# Adafruit_Bluefruit_LE_USB_Friend.net
KiCad netlist of a schematic drawn in EAGLE
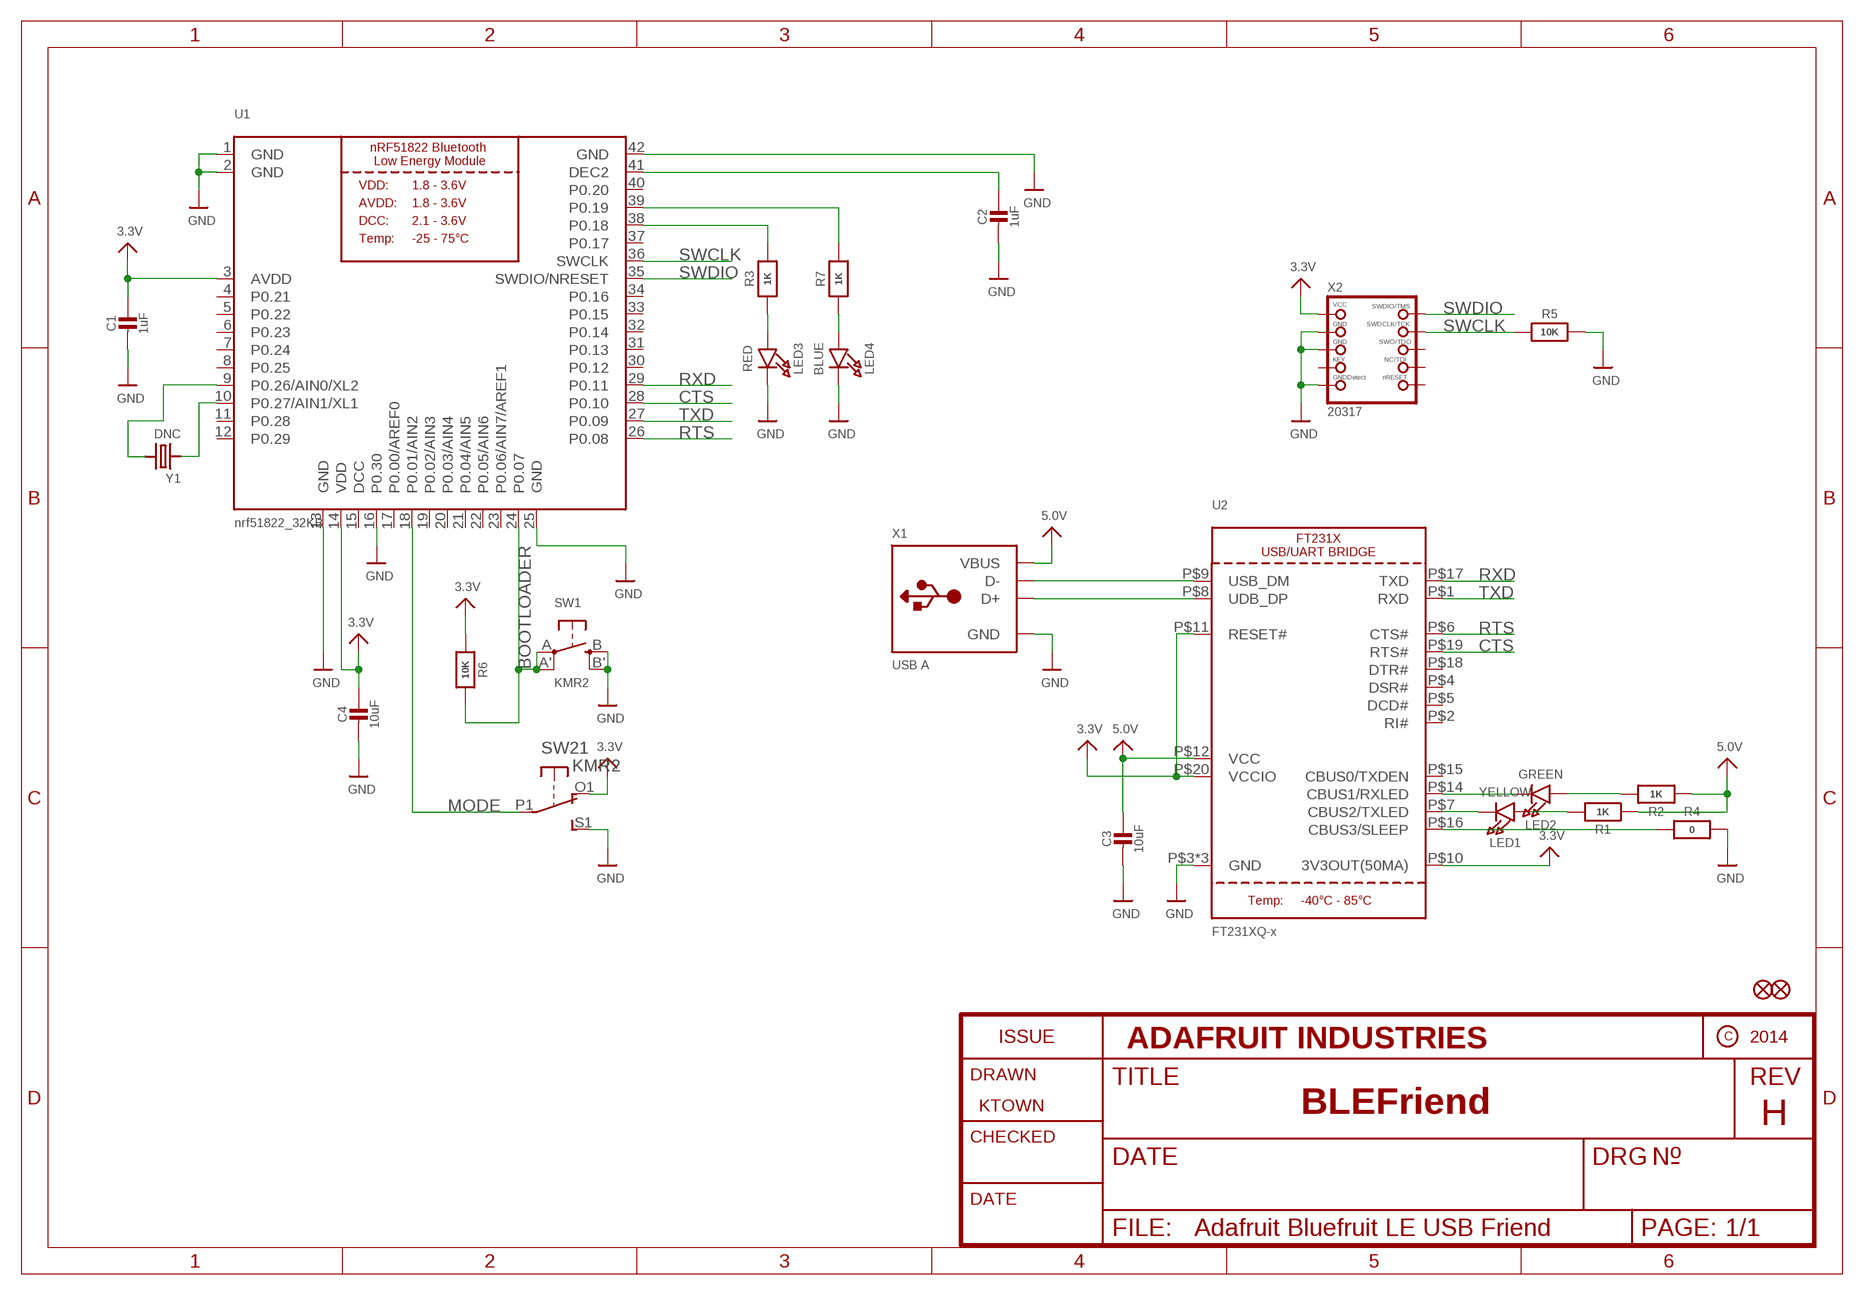
[diagram p0: schematic, sheet 1]

(export (version "E")
  (design (tool "Eeschema 10.0.6"))
  (components
    (comp (ref "C1")
      (value "1uF")
      (footprint "eagle-import:_0805MP")
      (libsource (lib "eagle-import") (part "CAP_CERAMIC_0805MP"))
    )
    (comp (ref "C2")
      (value "1uF")
      (footprint "eagle-import:_0805MP")
      (libsource (lib "eagle-import") (part "CAP_CERAMIC_0805MP"))
    )
    (comp (ref "C3")
      (value "10uF")
      (footprint "eagle-import:_0805MP")
      (libsource (lib "eagle-import") (part "CAP_CERAMIC_0805MP"))
    )
    (comp (ref "C4")
      (value "10uF")
      (footprint "eagle-import:_0805MP")
      (libsource (lib "eagle-import") (part "CAP_CERAMIC_0805MP"))
    )
    (comp (ref "FID1")
      (value "FIDUCIAL\"\"")
      (footprint "eagle-import:FIDUCIAL_1MM")
      (libsource (lib "eagle-import") (part "FIDUCIAL{dblquote}{dblquote}"))
    )
    (comp (ref "FID2")
      (value "FIDUCIAL\"\"")
      (footprint "eagle-import:FIDUCIAL_1MM")
      (libsource (lib "eagle-import") (part "FIDUCIAL{dblquote}{dblquote}"))
    )
    (comp (ref "LED1")
      (value "YELLOW")
      (footprint "eagle-import:CHIPLED_0805_NOOUTLINE")
      (libsource (lib "eagle-import") (part "LED0805_NOOUTLINE"))
    )
    (comp (ref "LED2")
      (value "GREEN")
      (footprint "eagle-import:CHIPLED_0805_NOOUTLINE")
      (libsource (lib "eagle-import") (part "LED0805_NOOUTLINE"))
    )
    (comp (ref "LED3")
      (value "RED")
      (footprint "eagle-import:CHIPLED_0805_NOOUTLINE")
      (libsource (lib "eagle-import") (part "LED0805_NOOUTLINE"))
    )
    (comp (ref "LED4")
      (value "BLUE")
      (footprint "eagle-import:CHIPLED_0805_NOOUTLINE")
      (libsource (lib "eagle-import") (part "LED0805_NOOUTLINE"))
    )
    (comp (ref "R1")
      (value "1K")
      (footprint "eagle-import:_0805MP")
      (libsource (lib "eagle-import") (part "RESISTOR_0805MP"))
    )
    (comp (ref "R2")
      (value "1K")
      (footprint "eagle-import:_0805MP")
      (libsource (lib "eagle-import") (part "RESISTOR_0805MP"))
    )
    (comp (ref "R3")
      (value "1K")
      (footprint "eagle-import:_0805MP")
      (libsource (lib "eagle-import") (part "RESISTOR_0805MP"))
    )
    (comp (ref "R4")
      (value "0")
      (footprint "eagle-import:_0805MP")
      (libsource (lib "eagle-import") (part "RESISTOR_0805MP"))
    )
    (comp (ref "R5")
      (value "10K")
      (footprint "eagle-import:_0805MP")
      (libsource (lib "eagle-import") (part "RESISTOR_0805MP"))
    )
    (comp (ref "R6")
      (value "10K")
      (footprint "eagle-import:_0805MP")
      (libsource (lib "eagle-import") (part "RESISTOR_0805MP"))
    )
    (comp (ref "R7")
      (value "1K")
      (footprint "eagle-import:_0805MP")
      (libsource (lib "eagle-import") (part "RESISTOR_0805MP"))
    )
    (comp (ref "SW1")
      (value "KMR2")
      (footprint "eagle-import:BTN_KMR2_4.6X2.8")
      (libsource (lib "eagle-import") (part "SWITCH_TACT_SMT4.6X2.8"))
    )
    (comp (ref "SW2")
      (value "KMR2")
      (footprint "eagle-import:EG1390")
      (libsource (lib "eagle-import") (part "DPDT-EG1390"))
    )
    (comp (ref "U1")
      (value "nrf51822_32KB")
      (footprint "eagle-import:BLE_MODULE_RAYTAC_MDBT40")
      (libsource (lib "eagle-import") (part "BLE_MODULE_RAYTAC_MDBT40"))
    )
    (comp (ref "U2")
      (value "FT231XQ-x")
      (footprint "eagle-import:QFN20_4MM")
      (libsource (lib "eagle-import") (part "FT231X"))
    )
    (comp (ref "X1")
      (value "USB A")
      (footprint "eagle-import:USB_A-THM")
      (libsource (lib "eagle-import") (part "USB_TYPEA_CLIENTTHM"))
    )
    (comp (ref "X2")
      (value "20317")
      (footprint "eagle-import:2X05_1.27MM_BOX_POSTS")
      (libsource (lib "eagle-import") (part "JTAG-CORTEXBOXPOSTS"))
    )
    (comp (ref "Y1")
      (value "DNC")
      (footprint "eagle-import:CRYSTAL_CYL_2X6MM_SMT")
      (libsource (lib "eagle-import") (part "CRYSTAL2.0X6.0_32.768"))
    )
  )
  (nets
    (net (code "1") (name "/BOOTLOADER") (class "Default")
      (node (ref "R6") (pin "2") (pinfunction "2_2") (pintype "passive"))
      (node (ref "SW1") (pin "A") (pinfunction "P_A") (pintype "passive"))
      (node (ref "SW1") (pin "A'") (pinfunction "P1_A'") (pintype "passive"))
      (node (ref "U1") (pin "24") (pinfunction "P0.07_24") (pintype "bidirectional"))
    )
    (net (code "2") (name "/CTS") (class "Default")
      (node (ref "U1") (pin "28") (pinfunction "P0.10_28") (pintype "bidirectional"))
      (node (ref "U2") (pin "P$19") (pinfunction "RTS#_P$19") (pintype "output"))
    )
    (net (code "3") (name "/DCC") (class "Default")
      (node (ref "U1") (pin "15") (pinfunction "DCC_15") (pintype "power_in"))
    )
    (net (code "4") (name "/MODE") (class "Default")
      (node (ref "SW2") (pin "P1") (pinfunction "P_P1") (pintype "passive"))
      (node (ref "U1") (pin "18") (pinfunction "P0.01/AIN2_18") (pintype "bidirectional"))
    )
    (net (code "5") (name "/RTS") (class "Default")
      (node (ref "U1") (pin "26") (pinfunction "P0.08_26") (pintype "bidirectional"))
      (node (ref "U2") (pin "P$6") (pinfunction "CTS#_P$6") (pintype "input"))
    )
    (net (code "6") (name "/RXD") (class "Default")
      (node (ref "U1") (pin "29") (pinfunction "P0.11_29") (pintype "bidirectional"))
      (node (ref "U2") (pin "P$17") (pinfunction "TXD_P$17") (pintype "output"))
    )
    (net (code "7") (name "/SWCLK") (class "Default")
      (node (ref "R5") (pin "1") (pinfunction "1_1") (pintype "passive"))
      (node (ref "U1") (pin "36") (pinfunction "SWCLK_36") (pintype "bidirectional"))
      (node (ref "X2") (pin "4") (pinfunction "SWDCLK_4") (pintype "bidirectional"))
    )
    (net (code "8") (name "/SWDIO") (class "Default")
      (node (ref "U1") (pin "35") (pinfunction "SWDIO/NRESET_35") (pintype "bidirectional"))
      (node (ref "X2") (pin "2") (pinfunction "SWDIO_2") (pintype "bidirectional"))
    )
    (net (code "9") (name "/TXD") (class "Default")
      (node (ref "U1") (pin "27") (pinfunction "P0.09_27") (pintype "bidirectional"))
      (node (ref "U2") (pin "P$1") (pinfunction "RXD_P$1") (pintype "input"))
    )
    (net (code "10") (name "3.3V") (class "Default")
      (node (ref "C1") (pin "1") (pinfunction "1_1") (pintype "passive"))
      (node (ref "C4") (pin "1") (pinfunction "1_1") (pintype "passive"))
      (node (ref "R6") (pin "1") (pinfunction "1_1") (pintype "passive"))
      (node (ref "SW2") (pin "O1") (pinfunction "O_O1") (pintype "passive"))
      (node (ref "U1") (pin "14") (pinfunction "VDD_14") (pintype "power_in"))
      (node (ref "U1") (pin "3") (pinfunction "AVDD_3") (pintype "power_in"))
      (node (ref "U2") (pin "P$10") (pinfunction "3V3OUT(50MA)_P$10") (pintype "power_in"))
      (node (ref "U2") (pin "P$11") (pinfunction "RESET#_P$11") (pintype "input"))
      (node (ref "U2") (pin "P$20") (pinfunction "VCCIO_P$20") (pintype "power_in"))
      (node (ref "X2") (pin "1") (pinfunction "VCC_1") (pintype "power_in"))
    )
    (net (code "11") (name "5.0V") (class "Default")
      (node (ref "C3") (pin "1") (pinfunction "1_1") (pintype "passive"))
      (node (ref "R1") (pin "1") (pinfunction "1_1") (pintype "passive"))
      (node (ref "R2") (pin "1") (pinfunction "1_1") (pintype "passive"))
      (node (ref "U2") (pin "P$12") (pinfunction "VCC_P$12") (pintype "power_in"))
      (node (ref "X1") (pin "VBUS") (pinfunction "VBUS_VBUS") (pintype "power_in"))
    )
    (net (code "12") (name "GND") (class "Default")
      (node (ref "C1") (pin "2") (pinfunction "2_2") (pintype "passive"))
      (node (ref "C2") (pin "2") (pinfunction "2_2") (pintype "passive"))
      (node (ref "C3") (pin "2") (pinfunction "2_2") (pintype "passive"))
      (node (ref "C4") (pin "2") (pinfunction "2_2") (pintype "passive"))
      (node (ref "LED3") (pin "C") (pinfunction "C_C") (pintype "passive"))
      (node (ref "LED4") (pin "C") (pinfunction "C_C") (pintype "passive"))
      (node (ref "R4") (pin "2") (pinfunction "2_2") (pintype "passive"))
      (node (ref "R5") (pin "2") (pinfunction "2_2") (pintype "passive"))
      (node (ref "SW1") (pin "B") (pinfunction "S_B") (pintype "passive"))
      (node (ref "SW1") (pin "B'") (pinfunction "S1_B'") (pintype "passive"))
      (node (ref "SW2") (pin "S1") (pinfunction "S_S1") (pintype "passive"))
      (node (ref "U1") (pin "1") (pinfunction "GND_1") (pintype "power_in"))
      (node (ref "U1") (pin "13") (pinfunction "GND_13") (pintype "power_in"))
      (node (ref "U1") (pin "16") (pinfunction "P0.30_16") (pintype "bidirectional"))
      (node (ref "U1") (pin "2") (pinfunction "GND_2") (pintype "power_in"))
      (node (ref "U1") (pin "25") (pinfunction "GND_25") (pintype "power_in"))
      (node (ref "U1") (pin "42") (pinfunction "GND_42") (pintype "power_in"))
      (node (ref "U2") (pin "P$13") (pinfunction "GND_P$13") (pintype "power_in"))
      (node (ref "U2") (pin "P$21") (pinfunction "GND_P$21") (pintype "power_in"))
      (node (ref "U2") (pin "P$3") (pinfunction "GND_P$3") (pintype "power_in"))
      (node (ref "X1") (pin "GND") (pinfunction "GND_GND") (pintype "power_in"))
      (node (ref "X2") (pin "3") (pinfunction "GND_3") (pintype "power_in"))
      (node (ref "X2") (pin "5") (pinfunction "GND_5") (pintype "power_in"))
      (node (ref "X2") (pin "9") (pinfunction "GNDDETECT_9") (pintype "bidirectional"))
    )
    (net (code "13") (name "Net-(LED1-PadA)") (class "Default")
      (node (ref "LED1") (pin "A") (pinfunction "A_A") (pintype "passive"))
      (node (ref "R1") (pin "2") (pinfunction "2_2") (pintype "passive"))
    )
    (net (code "14") (name "Net-(LED2-PadA)") (class "Default")
      (node (ref "LED2") (pin "A") (pinfunction "A_A") (pintype "passive"))
      (node (ref "R2") (pin "2") (pinfunction "2_2") (pintype "passive"))
    )
    (net (code "15") (name "Net-(LED3-PadA)") (class "Default")
      (node (ref "LED3") (pin "A") (pinfunction "A_A") (pintype "passive"))
      (node (ref "R3") (pin "1") (pinfunction "1_1") (pintype "passive"))
    )
    (net (code "16") (name "Net-(LED4-PadA)") (class "Default")
      (node (ref "LED4") (pin "A") (pinfunction "A_A") (pintype "passive"))
      (node (ref "R7") (pin "1") (pinfunction "1_1") (pintype "passive"))
    )
    (net (code "17") (name "Net-(U1-DEC2)") (class "Default")
      (node (ref "C2") (pin "1") (pinfunction "1_1") (pintype "passive"))
      (node (ref "U1") (pin "41") (pinfunction "DEC2_41") (pintype "power_in"))
    )
    (net (code "18") (name "Net-(U1-P0.18)") (class "Default")
      (node (ref "R3") (pin "2") (pinfunction "2_2") (pintype "passive"))
      (node (ref "U1") (pin "38") (pinfunction "P0.18_38") (pintype "bidirectional"))
    )
    (net (code "19") (name "Net-(U1-P0.19)") (class "Default")
      (node (ref "R7") (pin "2") (pinfunction "2_2") (pintype "passive"))
      (node (ref "U1") (pin "39") (pinfunction "P0.19_39") (pintype "bidirectional"))
    )
    (net (code "20") (name "Net-(U1-P0.26{slash}AIN0{slash}XL2)") (class "Default")
      (node (ref "U1") (pin "9") (pinfunction "P0.26/AIN0/XL2_9") (pintype "bidirectional"))
      (node (ref "Y1") (pin "2") (pinfunction "2_2") (pintype "passive"))
    )
    (net (code "21") (name "Net-(U1-P0.27{slash}AIN1{slash}XL1)") (class "Default")
      (node (ref "U1") (pin "10") (pinfunction "P0.27/AIN1/XL1_10") (pintype "bidirectional"))
      (node (ref "Y1") (pin "1") (pinfunction "1_1") (pintype "passive"))
    )
    (net (code "22") (name "Net-(U2-CBUS1{slash}RXLED)") (class "Default")
      (node (ref "LED2") (pin "C") (pinfunction "C_C") (pintype "passive"))
      (node (ref "U2") (pin "P$14") (pinfunction "CBUS1/RXLED_P$14") (pintype "bidirectional"))
    )
    (net (code "23") (name "Net-(U2-CBUS2{slash}TXLED)") (class "Default")
      (node (ref "LED1") (pin "C") (pinfunction "C_C") (pintype "passive"))
      (node (ref "U2") (pin "P$7") (pinfunction "CBUS2/TXLED_P$7") (pintype "bidirectional"))
    )
    (net (code "24") (name "Net-(U2-CBUS3{slash}SLEEP)") (class "Default")
      (node (ref "R4") (pin "1") (pinfunction "1_1") (pintype "passive"))
      (node (ref "U2") (pin "P$16") (pinfunction "CBUS3/SLEEP_P$16") (pintype "bidirectional"))
    )
    (net (code "25") (name "Net-(U2-UDB_DP)") (class "Default")
      (node (ref "U2") (pin "P$8") (pinfunction "UDB_DP_P$8") (pintype "input"))
      (node (ref "X1") (pin "D+") (pinfunction "D+_D+") (pintype "bidirectional"))
    )
    (net (code "26") (name "Net-(U2-USB_DM)") (class "Default")
      (node (ref "U2") (pin "P$9") (pinfunction "USB_DM_P$9") (pintype "input"))
      (node (ref "X1") (pin "D-") (pinfunction "D-_D-") (pintype "bidirectional"))
    )
    (net (code "27") (name "unconnected-(U1-P0.00{slash}AREF0-Pad17)") (class "Default")
      (node (ref "U1") (pin "17") (pinfunction "P0.00/AREF0_17") (pintype "bidirectional"))
    )
    (net (code "28") (name "unconnected-(U1-P0.02{slash}AIN3-Pad19)") (class "Default")
      (node (ref "U1") (pin "19") (pinfunction "P0.02/AIN3_19") (pintype "bidirectional"))
    )
    (net (code "29") (name "unconnected-(U1-P0.03{slash}AIN4-Pad20)") (class "Default")
      (node (ref "U1") (pin "20") (pinfunction "P0.03/AIN4_20") (pintype "bidirectional"))
    )
    (net (code "30") (name "unconnected-(U1-P0.04{slash}AIN5-Pad21)") (class "Default")
      (node (ref "U1") (pin "21") (pinfunction "P0.04/AIN5_21") (pintype "bidirectional"))
    )
    (net (code "31") (name "unconnected-(U1-P0.05{slash}AIN6-Pad22)") (class "Default")
      (node (ref "U1") (pin "22") (pinfunction "P0.05/AIN6_22") (pintype "bidirectional"))
    )
    (net (code "32") (name "unconnected-(U1-P0.06{slash}AIN7{slash}AREF1-Pad23)") (class "Default")
      (node (ref "U1") (pin "23") (pinfunction "P0.06/AIN7/AREF1_23") (pintype "bidirectional"))
    )
    (net (code "33") (name "unconnected-(U1-P0.12-Pad30)") (class "Default")
      (node (ref "U1") (pin "30") (pinfunction "P0.12_30") (pintype "bidirectional"))
    )
    (net (code "34") (name "unconnected-(U1-P0.13-Pad31)") (class "Default")
      (node (ref "U1") (pin "31") (pinfunction "P0.13_31") (pintype "bidirectional"))
    )
    (net (code "35") (name "unconnected-(U1-P0.14-Pad32)") (class "Default")
      (node (ref "U1") (pin "32") (pinfunction "P0.14_32") (pintype "bidirectional"))
    )
    (net (code "36") (name "unconnected-(U1-P0.15-Pad33)") (class "Default")
      (node (ref "U1") (pin "33") (pinfunction "P0.15_33") (pintype "bidirectional"))
    )
    (net (code "37") (name "unconnected-(U1-P0.16-Pad34)") (class "Default")
      (node (ref "U1") (pin "34") (pinfunction "P0.16_34") (pintype "bidirectional"))
    )
    (net (code "38") (name "unconnected-(U1-P0.17-Pad37)") (class "Default")
      (node (ref "U1") (pin "37") (pinfunction "P0.17_37") (pintype "bidirectional"))
    )
    (net (code "39") (name "unconnected-(U1-P0.20-Pad40)") (class "Default")
      (node (ref "U1") (pin "40") (pinfunction "P0.20_40") (pintype "bidirectional"))
    )
    (net (code "40") (name "unconnected-(U1-P0.21-Pad4)") (class "Default")
      (node (ref "U1") (pin "4") (pinfunction "P0.21_4") (pintype "bidirectional"))
    )
    (net (code "41") (name "unconnected-(U1-P0.22-Pad5)") (class "Default")
      (node (ref "U1") (pin "5") (pinfunction "P0.22_5") (pintype "bidirectional"))
    )
    (net (code "42") (name "unconnected-(U1-P0.23-Pad6)") (class "Default")
      (node (ref "U1") (pin "6") (pinfunction "P0.23_6") (pintype "bidirectional"))
    )
    (net (code "43") (name "unconnected-(U1-P0.24-Pad7)") (class "Default")
      (node (ref "U1") (pin "7") (pinfunction "P0.24_7") (pintype "bidirectional"))
    )
    (net (code "44") (name "unconnected-(U1-P0.25-Pad8)") (class "Default")
      (node (ref "U1") (pin "8") (pinfunction "P0.25_8") (pintype "bidirectional"))
    )
    (net (code "45") (name "unconnected-(U1-P0.28-Pad11)") (class "Default")
      (node (ref "U1") (pin "11") (pinfunction "P0.28_11") (pintype "bidirectional"))
    )
    (net (code "46") (name "unconnected-(U1-P0.29-Pad12)") (class "Default")
      (node (ref "U1") (pin "12") (pinfunction "P0.29_12") (pintype "bidirectional"))
    )
    (net (code "47") (name "unconnected-(U2-CBUS0{slash}TXDEN-PadP$15)") (class "Default")
      (node (ref "U2") (pin "P$15") (pinfunction "CBUS0/TXDEN_P$15") (pintype "bidirectional"))
    )
    (net (code "48") (name "unconnected-(U2-DCD#-PadP$5)") (class "Default")
      (node (ref "U2") (pin "P$5") (pinfunction "DCD#_P$5") (pintype "input"))
    )
    (net (code "49") (name "unconnected-(U2-DSR#-PadP$4)") (class "Default")
      (node (ref "U2") (pin "P$4") (pinfunction "DSR#_P$4") (pintype "input"))
    )
    (net (code "50") (name "unconnected-(U2-DTR#-PadP$18)") (class "Default")
      (node (ref "U2") (pin "P$18") (pinfunction "DTR#_P$18") (pintype "output"))
    )
    (net (code "51") (name "unconnected-(U2-RI#-PadP$2)") (class "Default")
      (node (ref "U2") (pin "P$2") (pinfunction "RI#_P$2") (pintype "input"))
    )
    (net (code "52") (name "unconnected-(X2-KEY-Pad7)") (class "Default")
      (node (ref "X2") (pin "7") (pinfunction "KEY_7") (pintype "bidirectional"))
    )
    (net (code "53") (name "unconnected-(X2-NRESET-Pad10)") (class "Default")
      (node (ref "X2") (pin "10") (pinfunction "NRESET_10") (pintype "bidirectional"))
    )
    (net (code "54") (name "unconnected-(X2-SWO-Pad6)") (class "Default")
      (node (ref "X2") (pin "6") (pinfunction "SWO_6") (pintype "bidirectional"))
    )
    (net (code "55") (name "unconnected-(X2-TDI-Pad8)") (class "Default")
      (node (ref "X2") (pin "8") (pinfunction "TDI_8") (pintype "bidirectional"))
    )
  )
)
